# doorball.net
KiCad netlist of a schematic drawn in EAGLE
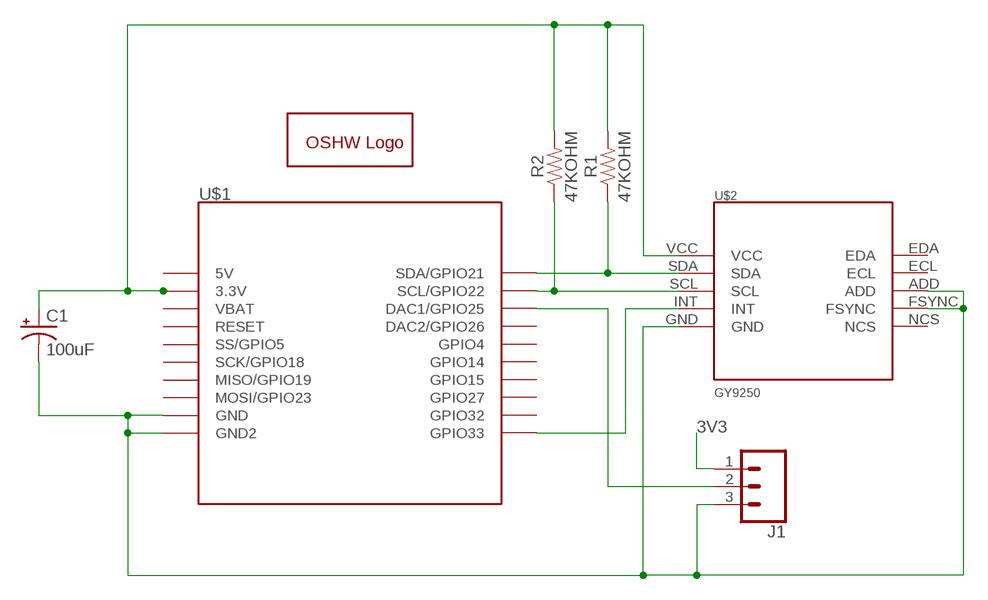
[diagram p0: schematic, sheet 1]

(export (version "E")
  (design (tool "Eeschema 10.0.6"))
  (components
    (comp (ref "C1")
      (value "100uF")
      (footprint "eagle-import:CPOL-RADIAL-2.5MM-6.5MM")
      (libsource (lib "eagle-import") (part "100UF-POLAR-RADIAL-2.5MM-25V-20%"))
    )
    (comp (ref "GOLD_ORB_SM1")
      (value "OSHWLOGOLOGO5MM")
      (footprint "eagle-import:OSHW_5MM")
      (libsource (lib "eagle-import") (part "OSHWLOGOLOGO5MM"))
    )
    (comp (ref "J1")
      (value "CONN_03")
      (footprint "eagle-import:1X03")
      (libsource (lib "eagle-import") (part "CONN_03"))
    )
    (comp (ref "R1")
      (value "47KOHM")
      (footprint "eagle-import:AXIAL-0.3-KIT")
      (libsource (lib "eagle-import") (part "47KOHM"))
    )
    (comp (ref "R2")
      (value "47KOHM")
      (footprint "eagle-import:AXIAL-0.3-KIT")
      (libsource (lib "eagle-import") (part "47KOHM"))
    )
    (comp (ref "U$1")
      (value "ESP23-TINY-PICO")
      (footprint "eagle-import:ESP32-TINY-PICO")
      (libsource (lib "eagle-import") (part "ESP23-TINY-PICO"))
    )
    (comp (ref "U$2")
      (value "GY9250")
      (footprint "eagle-import:GY9250BREAKOUT")
      (libsource (lib "eagle-import") (part "GY9250"))
    )
  )
  (nets
    (net (code "1") (name "/3V3") (class "Default")
      (node (ref "C1") (pin "1") (pinfunction "+_1") (pintype "passive"))
      (node (ref "J1") (pin "1") (pinfunction "1_1") (pintype "passive"))
      (node (ref "R1") (pin "P$2") (pinfunction "2_P$2") (pintype "passive"))
      (node (ref "R2") (pin "P$2") (pinfunction "2_P$2") (pintype "passive"))
      (node (ref "U$1") (pin "3.3V") (pinfunction "3.3V_3.3V") (pintype "power_in"))
      (node (ref "U$2") (pin "VCC") (pinfunction "VCC_VCC") (pintype "power_in"))
    )
    (net (code "2") (name "/5V") (class "Default")
      (node (ref "U$1") (pin "5V") (pinfunction "5V_5V") (pintype "power_in"))
    )
    (net (code "3") (name "Net-(C1--)") (class "Default")
      (node (ref "C1") (pin "2") (pinfunction "-_2") (pintype "passive"))
      (node (ref "J1") (pin "3") (pinfunction "3_3") (pintype "passive"))
      (node (ref "U$1") (pin "GND") (pinfunction "GND_GND") (pintype "power_in"))
      (node (ref "U$1") (pin "GND@2") (pinfunction "GND2_GND@2") (pintype "power_in"))
      (node (ref "U$2") (pin "ADD") (pinfunction "ADD_ADD") (pintype "bidirectional"))
      (node (ref "U$2") (pin "FSYNC") (pinfunction "FSYNC_FSYNC") (pintype "bidirectional"))
      (node (ref "U$2") (pin "GND") (pinfunction "GND_GND") (pintype "power_in"))
    )
    (net (code "4") (name "Net-(J1-Pad2)") (class "Default")
      (node (ref "J1") (pin "2") (pinfunction "2_2") (pintype "passive"))
      (node (ref "U$1") (pin "DAC1/GPIO25") (pinfunction "DAC1/GPIO25_DAC1/GPIO25") (pintype "bidirectional"))
    )
    (net (code "5") (name "Net-(R1-1)") (class "Default")
      (node (ref "R1") (pin "P$1") (pinfunction "1_P$1") (pintype "passive"))
      (node (ref "U$1") (pin "SDA/GPIO21") (pinfunction "SDA/GPIO21_SDA/GPIO21") (pintype "bidirectional"))
      (node (ref "U$2") (pin "SDA") (pinfunction "SDA_SDA") (pintype "bidirectional"))
    )
    (net (code "6") (name "Net-(R2-1)") (class "Default")
      (node (ref "R2") (pin "P$1") (pinfunction "1_P$1") (pintype "passive"))
      (node (ref "U$1") (pin "SCL/GPIO22") (pinfunction "SCL/GPIO22_SCL/GPIO22") (pintype "bidirectional"))
      (node (ref "U$2") (pin "SCL") (pinfunction "SCL_SCL") (pintype "bidirectional"))
    )
    (net (code "7") (name "Net-(U$1-PadGPIO33)") (class "Default")
      (node (ref "U$1") (pin "GPIO33") (pinfunction "GPIO33_GPIO33") (pintype "bidirectional"))
      (node (ref "U$2") (pin "INT") (pinfunction "INT_INT") (pintype "bidirectional"))
    )
    (net (code "8") (name "unconnected-(U$1-PadDAC2{slash}GPIO26)") (class "Default")
      (node (ref "U$1") (pin "DAC2/GPIO26") (pinfunction "DAC2/GPIO26_DAC2/GPIO26") (pintype "bidirectional"))
    )
    (net (code "9") (name "unconnected-(U$1-PadGPIO4)") (class "Default")
      (node (ref "U$1") (pin "GPIO4") (pinfunction "GPIO4_GPIO4") (pintype "bidirectional"))
    )
    (net (code "10") (name "unconnected-(U$1-PadGPIO14)") (class "Default")
      (node (ref "U$1") (pin "GPIO14") (pinfunction "GPIO14_GPIO14") (pintype "bidirectional"))
    )
    (net (code "11") (name "unconnected-(U$1-PadGPIO15)") (class "Default")
      (node (ref "U$1") (pin "GPIO15") (pinfunction "GPIO15_GPIO15") (pintype "bidirectional"))
    )
    (net (code "12") (name "unconnected-(U$1-PadGPIO27)") (class "Default")
      (node (ref "U$1") (pin "GPIO27") (pinfunction "GPIO27_GPIO27") (pintype "bidirectional"))
    )
    (net (code "13") (name "unconnected-(U$1-PadGPIO32)") (class "Default")
      (node (ref "U$1") (pin "GPIO32") (pinfunction "GPIO32_GPIO32") (pintype "bidirectional"))
    )
    (net (code "14") (name "unconnected-(U$1-PadMISO{slash}GPIO19)") (class "Default")
      (node (ref "U$1") (pin "MISO/GPIO19") (pinfunction "MISO/GPIO19_MISO/GPIO19") (pintype "input"))
    )
    (net (code "15") (name "unconnected-(U$1-PadMOSI{slash}GPIO23)") (class "Default")
      (node (ref "U$1") (pin "MOSI/GPIO23") (pinfunction "MOSI/GPIO23_MOSI/GPIO23") (pintype "output"))
    )
    (net (code "16") (name "unconnected-(U$1-PadRESET)") (class "Default")
      (node (ref "U$1") (pin "RESET") (pinfunction "RESET_RESET") (pintype "input"))
    )
    (net (code "17") (name "unconnected-(U$1-PadSCK{slash}GPIO18)") (class "Default")
      (node (ref "U$1") (pin "SCK/GPIO18") (pinfunction "SCK/GPIO18_SCK/GPIO18") (pintype "output"))
    )
    (net (code "18") (name "unconnected-(U$1-PadSS{slash}GPIO5)") (class "Default")
      (node (ref "U$1") (pin "SS/GPIO5") (pinfunction "SS/GPIO5_SS/GPIO5") (pintype "output"))
    )
    (net (code "19") (name "unconnected-(U$1-PadVBAT)") (class "Default")
      (node (ref "U$1") (pin "VBAT") (pinfunction "VBAT_VBAT") (pintype "output"))
    )
    (net (code "20") (name "unconnected-(U$2-PadECL)") (class "Default")
      (node (ref "U$2") (pin "ECL") (pinfunction "ECL_ECL") (pintype "bidirectional"))
    )
    (net (code "21") (name "unconnected-(U$2-PadEDA)") (class "Default")
      (node (ref "U$2") (pin "EDA") (pinfunction "EDA_EDA") (pintype "bidirectional"))
    )
    (net (code "22") (name "unconnected-(U$2-PadNCS)") (class "Default")
      (node (ref "U$2") (pin "NCS") (pinfunction "NCS_NCS") (pintype "bidirectional"))
    )
  )
)
